# 79x38_2P-BOB.net
KiCad netlist of a schematic drawn in EAGLE
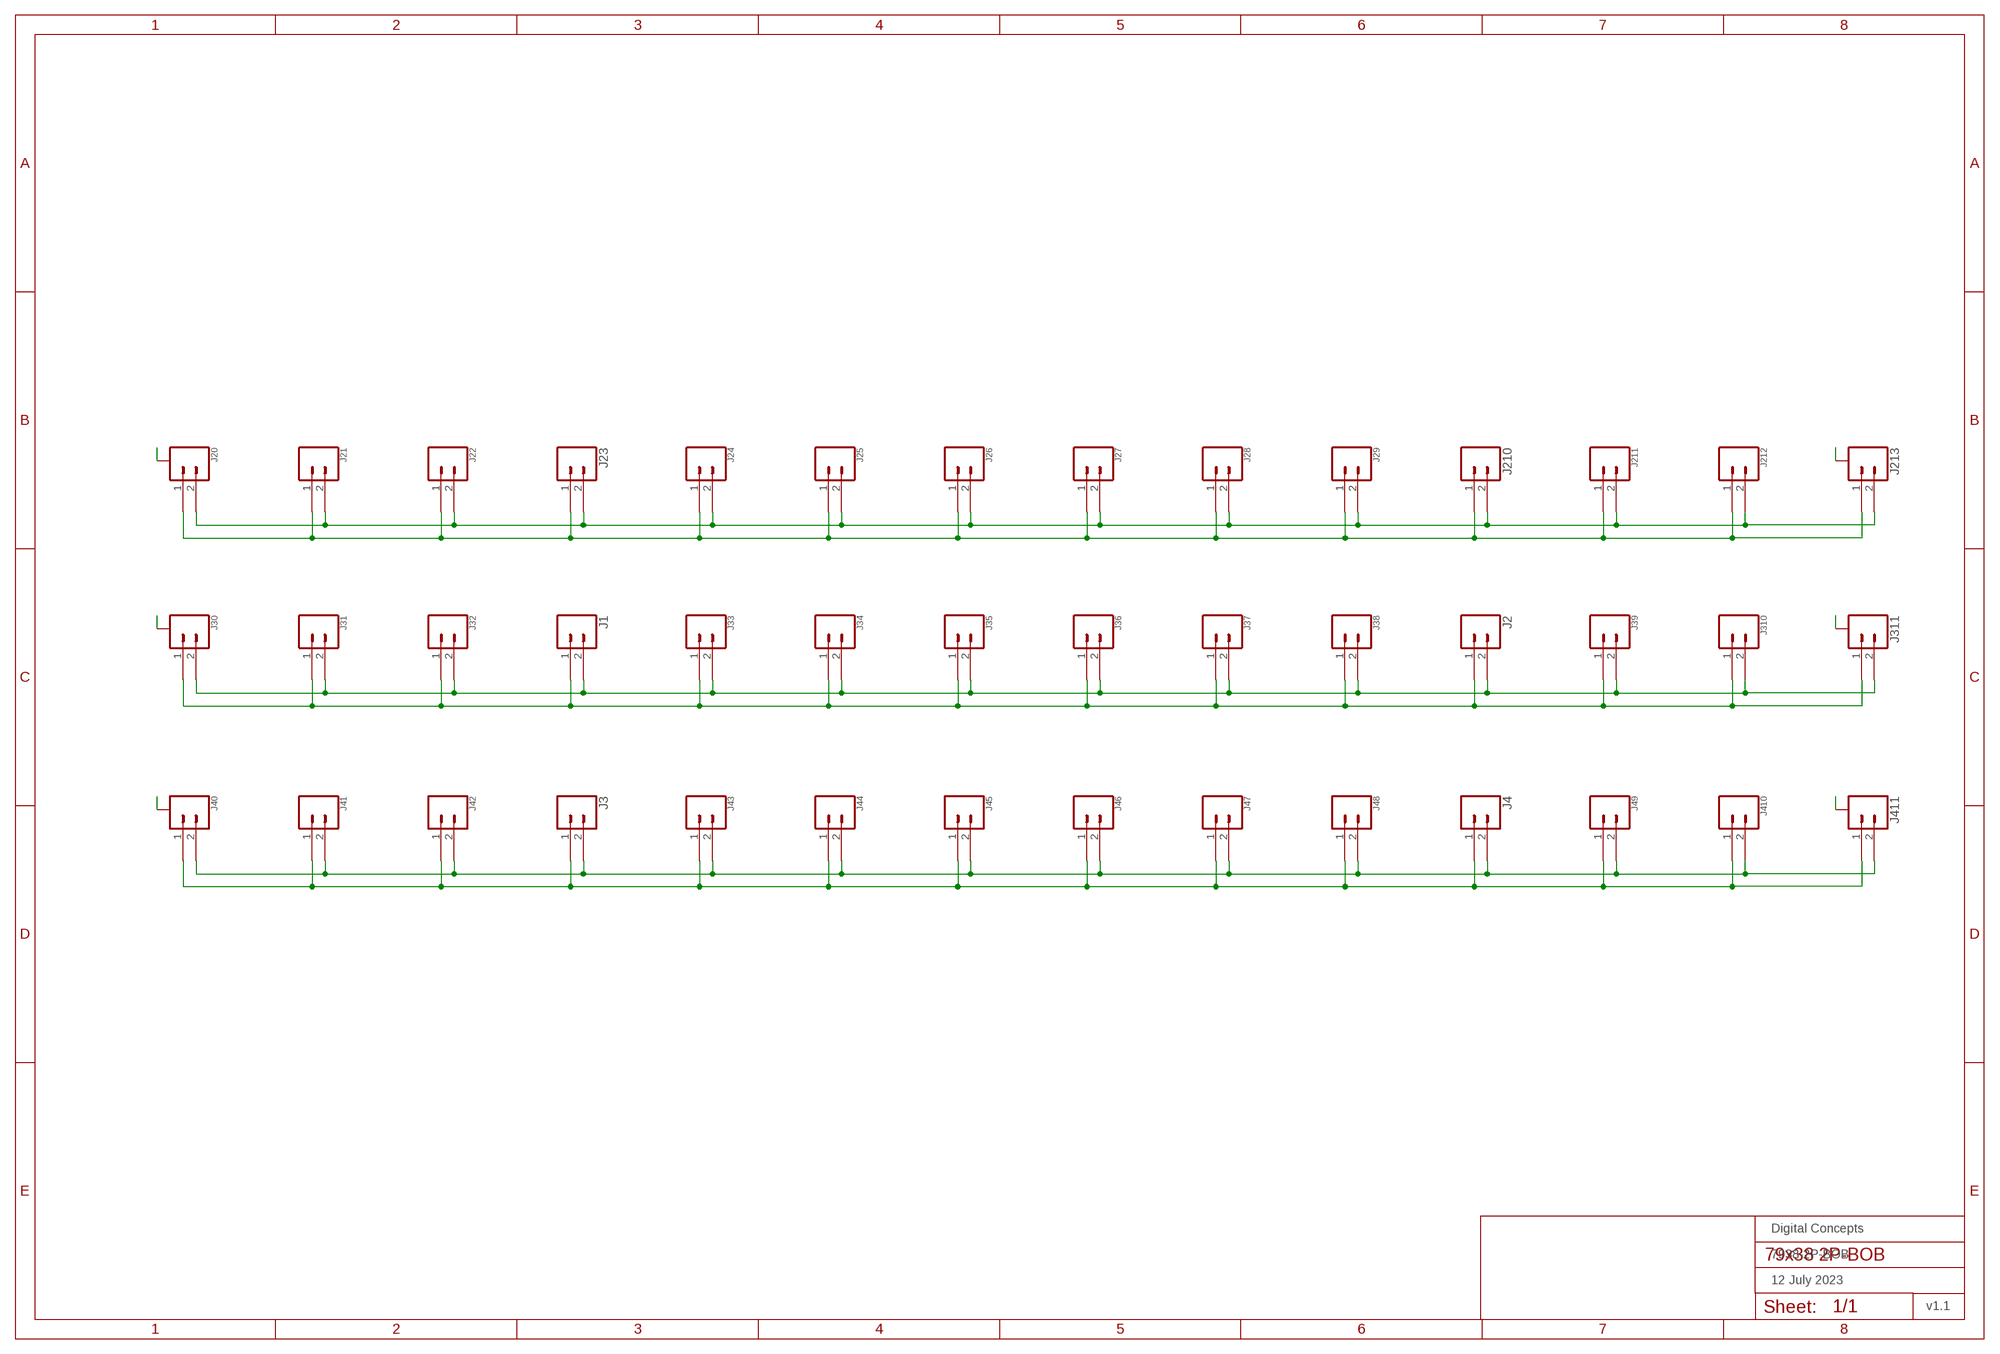
[diagram p0: schematic, sheet 1]

(export (version "E")
  (design (tool "Eeschema 10.0.6"))
  (components
    (comp (ref "J1")
      (value "JST-XH2.54-2-VERTICAL")
      (footprint "eagle-import:JST-XH2.4-2-VERTICAL")
      (libsource (lib "eagle-import") (part "JST-XH2.54-2-VERTICAL"))
    )
    (comp (ref "J2")
      (value "JST-XH2.54-2-VERTICAL")
      (footprint "eagle-import:JST-XH2.4-2-VERTICAL")
      (libsource (lib "eagle-import") (part "JST-XH2.54-2-VERTICAL"))
    )
    (comp (ref "J3")
      (value "JST-XH2.54-2-VERTICAL")
      (footprint "eagle-import:JST-XH2.4-2-VERTICAL")
      (libsource (lib "eagle-import") (part "JST-XH2.54-2-VERTICAL"))
    )
    (comp (ref "J4")
      (value "JST-XH2.54-2-VERTICAL")
      (footprint "eagle-import:JST-XH2.4-2-VERTICAL")
      (libsource (lib "eagle-import") (part "JST-XH2.54-2-VERTICAL"))
    )
    (comp (ref "J20")
      (value "JST-SH1.0-2-SMD-VERTICAL")
      (footprint "eagle-import:JST-SH1.0-2-VERTICAL")
      (libsource (lib "eagle-import") (part "JST-SH1.0-2-SMD-VERTICAL"))
    )
    (comp (ref "J21")
      (value "JST-GH1.25-2-VERTICAL")
      (footprint "eagle-import:JST-GH1.25-2-VERTICAL")
      (libsource (lib "eagle-import") (part "JST-GH1.25-2-VERTICAL"))
    )
    (comp (ref "J22")
      (value "JST-PH2.0-2-VERTICAL")
      (footprint "eagle-import:JST-PH2.0-2-VERTICAL")
      (libsource (lib "eagle-import") (part "JST-PH2.0-2-VERTICAL"))
    )
    (comp (ref "J23")
      (value "JST-XH2.54-2-VERTICAL")
      (footprint "eagle-import:JST-XH2.4-2-VERTICAL")
      (libsource (lib "eagle-import") (part "JST-XH2.54-2-VERTICAL"))
    )
    (comp (ref "J24")
      (value "HEADER-1X2-GENERIC")
      (footprint "eagle-import:CONN_02-GENERIC")
      (libsource (lib "eagle-import") (part "HEADER-1X2-GENERIC"))
    )
    (comp (ref "J25")
      (value "HEADER-1X2-GENERIC")
      (footprint "eagle-import:CONN_02-GENERIC")
      (libsource (lib "eagle-import") (part "HEADER-1X2-GENERIC"))
    )
    (comp (ref "J26")
      (value "HEADER-1X2-GENERIC")
      (footprint "eagle-import:CONN_02-GENERIC")
      (libsource (lib "eagle-import") (part "HEADER-1X2-GENERIC"))
    )
    (comp (ref "J27")
      (value "HEADER-1X2-GENERIC")
      (footprint "eagle-import:CONN_02-GENERIC")
      (libsource (lib "eagle-import") (part "HEADER-1X2-GENERIC"))
    )
    (comp (ref "J28")
      (value "HEADER-1X2-GENERIC")
      (footprint "eagle-import:CONN_02-GENERIC")
      (libsource (lib "eagle-import") (part "HEADER-1X2-GENERIC"))
    )
    (comp (ref "J29")
      (value "HEADER-1X2-GENERIC")
      (footprint "eagle-import:CONN_02-GENERIC")
      (libsource (lib "eagle-import") (part "HEADER-1X2-GENERIC"))
    )
    (comp (ref "J30")
      (value "JST-SH1.0-2-SMD-VERTICAL")
      (footprint "eagle-import:JST-SH1.0-2-VERTICAL")
      (libsource (lib "eagle-import") (part "JST-SH1.0-2-SMD-VERTICAL"))
    )
    (comp (ref "J31")
      (value "JST-GH1.25-2-VERTICAL")
      (footprint "eagle-import:JST-GH1.25-2-VERTICAL")
      (libsource (lib "eagle-import") (part "JST-GH1.25-2-VERTICAL"))
    )
    (comp (ref "J32")
      (value "JST-PH2.0-2-VERTICAL")
      (footprint "eagle-import:JST-PH2.0-2-VERTICAL")
      (libsource (lib "eagle-import") (part "JST-PH2.0-2-VERTICAL"))
    )
    (comp (ref "J33")
      (value "HEADER-1X2-GENERIC")
      (footprint "eagle-import:CONN_02-GENERIC")
      (libsource (lib "eagle-import") (part "HEADER-1X2-GENERIC"))
    )
    (comp (ref "J34")
      (value "HEADER-1X2-GENERIC")
      (footprint "eagle-import:CONN_02-GENERIC")
      (libsource (lib "eagle-import") (part "HEADER-1X2-GENERIC"))
    )
    (comp (ref "J35")
      (value "HEADER-1X2-GENERIC")
      (footprint "eagle-import:CONN_02-GENERIC")
      (libsource (lib "eagle-import") (part "HEADER-1X2-GENERIC"))
    )
    (comp (ref "J36")
      (value "HEADER-1X2-GENERIC")
      (footprint "eagle-import:CONN_02-GENERIC")
      (libsource (lib "eagle-import") (part "HEADER-1X2-GENERIC"))
    )
    (comp (ref "J37")
      (value "HEADER-1X2-GENERIC")
      (footprint "eagle-import:CONN_02-GENERIC")
      (libsource (lib "eagle-import") (part "HEADER-1X2-GENERIC"))
    )
    (comp (ref "J38")
      (value "HEADER-1X2-GENERIC")
      (footprint "eagle-import:CONN_02-GENERIC")
      (libsource (lib "eagle-import") (part "HEADER-1X2-GENERIC"))
    )
    (comp (ref "J39")
      (value "JST-PH2.0-2-VERTICAL")
      (footprint "eagle-import:JST-PH2.0-2-VERTICAL")
      (libsource (lib "eagle-import") (part "JST-PH2.0-2-VERTICAL"))
    )
    (comp (ref "J40")
      (value "JST-SH1.0-2-SMD-VERTICAL")
      (footprint "eagle-import:JST-SH1.0-2-VERTICAL")
      (libsource (lib "eagle-import") (part "JST-SH1.0-2-SMD-VERTICAL"))
    )
    (comp (ref "J41")
      (value "JST-GH1.25-2-VERTICAL")
      (footprint "eagle-import:JST-GH1.25-2-VERTICAL")
      (libsource (lib "eagle-import") (part "JST-GH1.25-2-VERTICAL"))
    )
    (comp (ref "J42")
      (value "JST-PH2.0-2-VERTICAL")
      (footprint "eagle-import:JST-PH2.0-2-VERTICAL")
      (libsource (lib "eagle-import") (part "JST-PH2.0-2-VERTICAL"))
    )
    (comp (ref "J43")
      (value "HEADER-1X2-GENERIC")
      (footprint "eagle-import:CONN_02-GENERIC")
      (libsource (lib "eagle-import") (part "HEADER-1X2-GENERIC"))
    )
    (comp (ref "J44")
      (value "HEADER-1X2-GENERIC")
      (footprint "eagle-import:CONN_02-GENERIC")
      (libsource (lib "eagle-import") (part "HEADER-1X2-GENERIC"))
    )
    (comp (ref "J45")
      (value "HEADER-1X2-GENERIC")
      (footprint "eagle-import:CONN_02-GENERIC")
      (libsource (lib "eagle-import") (part "HEADER-1X2-GENERIC"))
    )
    (comp (ref "J46")
      (value "HEADER-1X2-GENERIC")
      (footprint "eagle-import:CONN_02-GENERIC")
      (libsource (lib "eagle-import") (part "HEADER-1X2-GENERIC"))
    )
    (comp (ref "J47")
      (value "HEADER-1X2-GENERIC")
      (footprint "eagle-import:CONN_02-GENERIC")
      (libsource (lib "eagle-import") (part "HEADER-1X2-GENERIC"))
    )
    (comp (ref "J48")
      (value "HEADER-1X2-GENERIC")
      (footprint "eagle-import:CONN_02-GENERIC")
      (libsource (lib "eagle-import") (part "HEADER-1X2-GENERIC"))
    )
    (comp (ref "J49")
      (value "JST-PH2.0-2-VERTICAL")
      (footprint "eagle-import:JST-PH2.0-2-VERTICAL")
      (libsource (lib "eagle-import") (part "JST-PH2.0-2-VERTICAL"))
    )
    (comp (ref "J210")
      (value "JST-XH2.54-2-VERTICAL")
      (footprint "eagle-import:JST-XH2.4-2-VERTICAL")
      (libsource (lib "eagle-import") (part "JST-XH2.54-2-VERTICAL"))
    )
    (comp (ref "J211")
      (value "JST-PH2.0-2-VERTICAL")
      (footprint "eagle-import:JST-PH2.0-2-VERTICAL")
      (libsource (lib "eagle-import") (part "JST-PH2.0-2-VERTICAL"))
    )
    (comp (ref "J212")
      (value "JST-GH1.25-2-VERTICAL")
      (footprint "eagle-import:JST-GH1.25-2-VERTICAL")
      (libsource (lib "eagle-import") (part "JST-GH1.25-2-VERTICAL"))
    )
    (comp (ref "J213")
      (value "JST-SH1.0-2-SMD-VERTICAL")
      (footprint "eagle-import:JST-SH1.0-2-VERTICAL")
      (libsource (lib "eagle-import") (part "JST-SH1.0-2-SMD-VERTICAL"))
    )
    (comp (ref "J310")
      (value "JST-GH1.25-2-VERTICAL")
      (footprint "eagle-import:JST-GH1.25-2-VERTICAL")
      (libsource (lib "eagle-import") (part "JST-GH1.25-2-VERTICAL"))
    )
    (comp (ref "J311")
      (value "JST-SH1.0-2-SMD-VERTICAL")
      (footprint "eagle-import:JST-SH1.0-2-VERTICAL")
      (libsource (lib "eagle-import") (part "JST-SH1.0-2-SMD-VERTICAL"))
    )
    (comp (ref "J410")
      (value "JST-GH1.25-2-VERTICAL")
      (footprint "eagle-import:JST-GH1.25-2-VERTICAL")
      (libsource (lib "eagle-import") (part "JST-GH1.25-2-VERTICAL"))
    )
    (comp (ref "J411")
      (value "JST-SH1.0-2-SMD-VERTICAL")
      (footprint "eagle-import:JST-SH1.0-2-VERTICAL")
      (libsource (lib "eagle-import") (part "JST-SH1.0-2-SMD-VERTICAL"))
    )
  )
  (nets
    (net (code "1") (name "/A") (class "Default")
      (node (ref "J20") (pin "A@1") (pinfunction "A_A@1") (pintype "power_in"))
      (node (ref "J20") (pin "A@2") (pinfunction "A_A@2") (pintype "power_in"))
      (node (ref "J213") (pin "A@1") (pinfunction "A_A@1") (pintype "power_in"))
      (node (ref "J213") (pin "A@2") (pinfunction "A_A@2") (pintype "power_in"))
      (node (ref "J30") (pin "A@1") (pinfunction "A_A@1") (pintype "power_in"))
      (node (ref "J30") (pin "A@2") (pinfunction "A_A@2") (pintype "power_in"))
      (node (ref "J311") (pin "A@1") (pinfunction "A_A@1") (pintype "power_in"))
      (node (ref "J311") (pin "A@2") (pinfunction "A_A@2") (pintype "power_in"))
      (node (ref "J40") (pin "A@1") (pinfunction "A_A@1") (pintype "power_in"))
      (node (ref "J40") (pin "A@2") (pinfunction "A_A@2") (pintype "power_in"))
      (node (ref "J411") (pin "A@1") (pinfunction "A_A@1") (pintype "power_in"))
      (node (ref "J411") (pin "A@2") (pinfunction "A_A@2") (pintype "power_in"))
    )
    (net (code "2") (name "Net-(J1-Pad1)") (class "Default")
      (node (ref "J1") (pin "1") (pinfunction "1_1") (pintype "passive"))
      (node (ref "J2") (pin "1") (pinfunction "1_1") (pintype "passive"))
      (node (ref "J30") (pin "1") (pinfunction "1_1") (pintype "passive"))
      (node (ref "J31") (pin "1") (pinfunction "1_1") (pintype "passive"))
      (node (ref "J310") (pin "1") (pinfunction "1_1") (pintype "passive"))
      (node (ref "J311") (pin "1") (pinfunction "1_1") (pintype "passive"))
      (node (ref "J32") (pin "1") (pinfunction "1_1") (pintype "passive"))
      (node (ref "J33") (pin "1") (pinfunction "1_1") (pintype "passive"))
      (node (ref "J34") (pin "1") (pinfunction "1_1") (pintype "passive"))
      (node (ref "J35") (pin "1") (pinfunction "1_1") (pintype "passive"))
      (node (ref "J36") (pin "1") (pinfunction "1_1") (pintype "passive"))
      (node (ref "J37") (pin "1") (pinfunction "1_1") (pintype "passive"))
      (node (ref "J38") (pin "1") (pinfunction "1_1") (pintype "passive"))
      (node (ref "J39") (pin "1") (pinfunction "1_1") (pintype "passive"))
    )
    (net (code "3") (name "Net-(J1-Pad2)") (class "Default")
      (node (ref "J1") (pin "2") (pinfunction "2_2") (pintype "passive"))
      (node (ref "J2") (pin "2") (pinfunction "2_2") (pintype "passive"))
      (node (ref "J30") (pin "2") (pinfunction "2_2") (pintype "passive"))
      (node (ref "J31") (pin "2") (pinfunction "2_2") (pintype "passive"))
      (node (ref "J310") (pin "2") (pinfunction "2_2") (pintype "passive"))
      (node (ref "J311") (pin "2") (pinfunction "2_2") (pintype "passive"))
      (node (ref "J32") (pin "2") (pinfunction "2_2") (pintype "passive"))
      (node (ref "J33") (pin "2") (pinfunction "2_2") (pintype "passive"))
      (node (ref "J34") (pin "2") (pinfunction "2_2") (pintype "passive"))
      (node (ref "J35") (pin "2") (pinfunction "2_2") (pintype "passive"))
      (node (ref "J36") (pin "2") (pinfunction "2_2") (pintype "passive"))
      (node (ref "J37") (pin "2") (pinfunction "2_2") (pintype "passive"))
      (node (ref "J38") (pin "2") (pinfunction "2_2") (pintype "passive"))
      (node (ref "J39") (pin "2") (pinfunction "2_2") (pintype "passive"))
    )
    (net (code "4") (name "Net-(J3-Pad1)") (class "Default")
      (node (ref "J3") (pin "1") (pinfunction "1_1") (pintype "passive"))
      (node (ref "J4") (pin "1") (pinfunction "1_1") (pintype "passive"))
      (node (ref "J40") (pin "1") (pinfunction "1_1") (pintype "passive"))
      (node (ref "J41") (pin "1") (pinfunction "1_1") (pintype "passive"))
      (node (ref "J410") (pin "1") (pinfunction "1_1") (pintype "passive"))
      (node (ref "J411") (pin "1") (pinfunction "1_1") (pintype "passive"))
      (node (ref "J42") (pin "1") (pinfunction "1_1") (pintype "passive"))
      (node (ref "J43") (pin "1") (pinfunction "1_1") (pintype "passive"))
      (node (ref "J44") (pin "1") (pinfunction "1_1") (pintype "passive"))
      (node (ref "J45") (pin "1") (pinfunction "1_1") (pintype "passive"))
      (node (ref "J46") (pin "1") (pinfunction "1_1") (pintype "passive"))
      (node (ref "J47") (pin "1") (pinfunction "1_1") (pintype "passive"))
      (node (ref "J48") (pin "1") (pinfunction "1_1") (pintype "passive"))
      (node (ref "J49") (pin "1") (pinfunction "1_1") (pintype "passive"))
    )
    (net (code "5") (name "Net-(J3-Pad2)") (class "Default")
      (node (ref "J3") (pin "2") (pinfunction "2_2") (pintype "passive"))
      (node (ref "J4") (pin "2") (pinfunction "2_2") (pintype "passive"))
      (node (ref "J40") (pin "2") (pinfunction "2_2") (pintype "passive"))
      (node (ref "J41") (pin "2") (pinfunction "2_2") (pintype "passive"))
      (node (ref "J410") (pin "2") (pinfunction "2_2") (pintype "passive"))
      (node (ref "J411") (pin "2") (pinfunction "2_2") (pintype "passive"))
      (node (ref "J42") (pin "2") (pinfunction "2_2") (pintype "passive"))
      (node (ref "J43") (pin "2") (pinfunction "2_2") (pintype "passive"))
      (node (ref "J44") (pin "2") (pinfunction "2_2") (pintype "passive"))
      (node (ref "J45") (pin "2") (pinfunction "2_2") (pintype "passive"))
      (node (ref "J46") (pin "2") (pinfunction "2_2") (pintype "passive"))
      (node (ref "J47") (pin "2") (pinfunction "2_2") (pintype "passive"))
      (node (ref "J48") (pin "2") (pinfunction "2_2") (pintype "passive"))
      (node (ref "J49") (pin "2") (pinfunction "2_2") (pintype "passive"))
    )
    (net (code "6") (name "Net-(J20-Pad1)") (class "Default")
      (node (ref "J20") (pin "1") (pinfunction "1_1") (pintype "passive"))
      (node (ref "J21") (pin "1") (pinfunction "1_1") (pintype "passive"))
      (node (ref "J210") (pin "1") (pinfunction "1_1") (pintype "passive"))
      (node (ref "J211") (pin "1") (pinfunction "1_1") (pintype "passive"))
      (node (ref "J212") (pin "1") (pinfunction "1_1") (pintype "passive"))
      (node (ref "J213") (pin "1") (pinfunction "1_1") (pintype "passive"))
      (node (ref "J22") (pin "1") (pinfunction "1_1") (pintype "passive"))
      (node (ref "J23") (pin "1") (pinfunction "1_1") (pintype "passive"))
      (node (ref "J24") (pin "1") (pinfunction "1_1") (pintype "passive"))
      (node (ref "J25") (pin "1") (pinfunction "1_1") (pintype "passive"))
      (node (ref "J26") (pin "1") (pinfunction "1_1") (pintype "passive"))
      (node (ref "J27") (pin "1") (pinfunction "1_1") (pintype "passive"))
      (node (ref "J28") (pin "1") (pinfunction "1_1") (pintype "passive"))
      (node (ref "J29") (pin "1") (pinfunction "1_1") (pintype "passive"))
    )
    (net (code "7") (name "Net-(J20-Pad2)") (class "Default")
      (node (ref "J20") (pin "2") (pinfunction "2_2") (pintype "passive"))
      (node (ref "J21") (pin "2") (pinfunction "2_2") (pintype "passive"))
      (node (ref "J210") (pin "2") (pinfunction "2_2") (pintype "passive"))
      (node (ref "J211") (pin "2") (pinfunction "2_2") (pintype "passive"))
      (node (ref "J212") (pin "2") (pinfunction "2_2") (pintype "passive"))
      (node (ref "J213") (pin "2") (pinfunction "2_2") (pintype "passive"))
      (node (ref "J22") (pin "2") (pinfunction "2_2") (pintype "passive"))
      (node (ref "J23") (pin "2") (pinfunction "2_2") (pintype "passive"))
      (node (ref "J24") (pin "2") (pinfunction "2_2") (pintype "passive"))
      (node (ref "J25") (pin "2") (pinfunction "2_2") (pintype "passive"))
      (node (ref "J26") (pin "2") (pinfunction "2_2") (pintype "passive"))
      (node (ref "J27") (pin "2") (pinfunction "2_2") (pintype "passive"))
      (node (ref "J28") (pin "2") (pinfunction "2_2") (pintype "passive"))
      (node (ref "J29") (pin "2") (pinfunction "2_2") (pintype "passive"))
    )
  )
)
